# Sheet1.net
KiCad netlist of a schematic drawn in Altium Designer
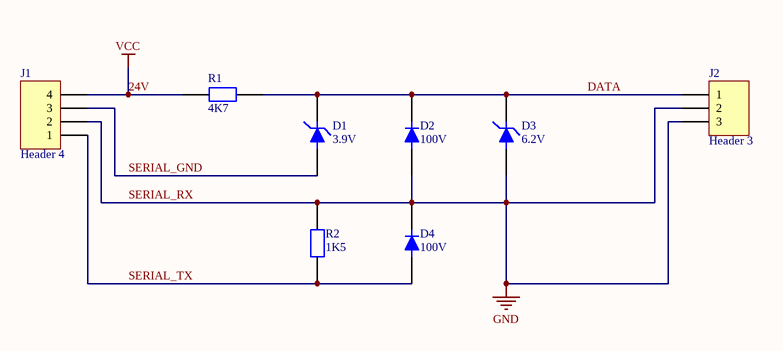
[diagram p0: Sheet1.SchDoc]

(export (version "E")
  (design (tool "Eeschema 10.0.6"))
  (components
    (comp (ref "D1")
      (value "3.9V")
      (footprint "SOT23")
      (description "DIODE ZENER 3.9V 225MW SOT23-3")
      (fields
        (field (name "MANUFACTURER") "ON Semiconductor")
        (field (name "MANUFACTURER PART NUMBER") "BZX84C3V9LT1G")
      )
      (libsource (lib "Schlib1") (part "BZX84C3V9LT1G"))
    )
    (comp (ref "D2")
      (value "100V")
      (footprint "SOT23")
      (description "DIODE SCHOTTKY 100V 150MA SOT23")
      (fields
        (field (name "MANUFACTURER") "STMicroelectronics")
        (field (name "MANUFACTURER PART NUMBER") "BAR46FILM")
      )
      (libsource (lib "Schlib1") (part "BAR46FILM"))
    )
    (comp (ref "D3")
      (value "6.2V")
      (footprint "SOT23")
      (description "DIODE ZENER 6.2V 225MW SOT23-3")
      (fields
        (field (name "MANUFACTURER") "ON Semiconductor")
        (field (name "MANUFACTURER PART NUMBER") "BZX84C6V2LT1G")
      )
      (libsource (lib "Schlib1") (part "BZX84C6V2LT1G"))
    )
    (comp (ref "D4")
      (value "100V")
      (footprint "SOT23")
      (description "DIODE SCHOTTKY 100V 150MA SOT23")
      (fields
        (field (name "MANUFACTURER") "STMicroelectronics")
        (field (name "MANUFACTURER PART NUMBER") "BAR46FILM")
      )
      (libsource (lib "Schlib1") (part "BAR46FILM"))
    )
    (comp (ref "J1")
      (value "Header 4")
      (footprint "HDR1X4")
      (description "Header, 4-Pin")
      (fields (field (name "PUBLISHER") "Altium Limited"))
      (libsource (lib "Miscellaneous Connectors") (part "Header 4"))
    )
    (comp (ref "J2")
      (value "Header 3")
      (footprint "PH_TERM_3")
      (description "Header, 3-Pin")
      (fields (field (name "PUBLISHER") "Altium Limited"))
      (libsource (lib "Miscellaneous Connectors") (part "Header 3"))
    )
    (comp (ref "R1")
      (value "4K7")
      (footprint "RESC1608")
      (description "RES SMD 4.7K OHM 1% 1/10W 0603")
      (fields
        (field (name "MANUFACTURER") "Yageo")
        (field (name "MANUFACTURER PART NUMBER") "RC0603FR-074K7L")
      )
      (libsource (lib "Schlib1") (part "RC0603FR-074K7L"))
    )
    (comp (ref "R2")
      (value "1K5")
      (footprint "RESC1608")
      (description "RES SMD 1.5K OHM 1% 1/10W 0603")
      (fields
        (field (name "MANUFACTURER") "Yageo")
        (field (name "MANUFACTURER PART NUMBER") "RC0603FR-071K5L")
      )
      (libsource (lib "Schlib1") (part "RC0603FR-071K5L"))
    )
  )
  (nets
    (net (code "1") (name "/DATA") (class "Default")
      (node (ref "D1") (pin "3") (pinfunction "3_3") (pintype "passive"))
      (node (ref "D2") (pin "3") (pinfunction "3_3") (pintype "passive"))
      (node (ref "D3") (pin "3") (pinfunction "3_3") (pintype "passive"))
      (node (ref "J2") (pin "1") (pinfunction "1_1") (pintype "passive"))
      (node (ref "R1") (pin "2") (pinfunction "2_2") (pintype "passive"))
    )
    (net (code "2") (name "/SERIAL_GND") (class "Default")
      (node (ref "D1") (pin "1") (pinfunction "1_1") (pintype "passive"))
      (node (ref "J1") (pin "3") (pinfunction "3_3") (pintype "passive"))
    )
    (net (code "3") (name "/SERIAL_TX") (class "Default")
      (node (ref "D4") (pin "1") (pinfunction "1_1") (pintype "passive"))
      (node (ref "J1") (pin "1") (pinfunction "1_1") (pintype "passive"))
      (node (ref "R2") (pin "1") (pinfunction "1_1") (pintype "passive"))
    )
    (net (code "4") (name "GND") (class "Default")
      (node (ref "D2") (pin "1") (pinfunction "1_1") (pintype "passive"))
      (node (ref "D3") (pin "1") (pinfunction "1_1") (pintype "passive"))
      (node (ref "D4") (pin "3") (pinfunction "3_3") (pintype "passive"))
      (node (ref "J1") (pin "2") (pinfunction "2_2") (pintype "passive"))
      (node (ref "J2") (pin "2") (pinfunction "2_2") (pintype "passive"))
      (node (ref "J2") (pin "3") (pinfunction "3_3") (pintype "passive"))
      (node (ref "R2") (pin "2") (pinfunction "2_2") (pintype "passive"))
    )
    (net (code "5") (name "VCC") (class "Default")
      (node (ref "J1") (pin "4") (pinfunction "4_4") (pintype "passive"))
      (node (ref "R1") (pin "1") (pinfunction "1_1") (pintype "passive"))
    )
  )
)
